# LED_driver_final.net
KiCad netlist of a schematic drawn in EAGLE
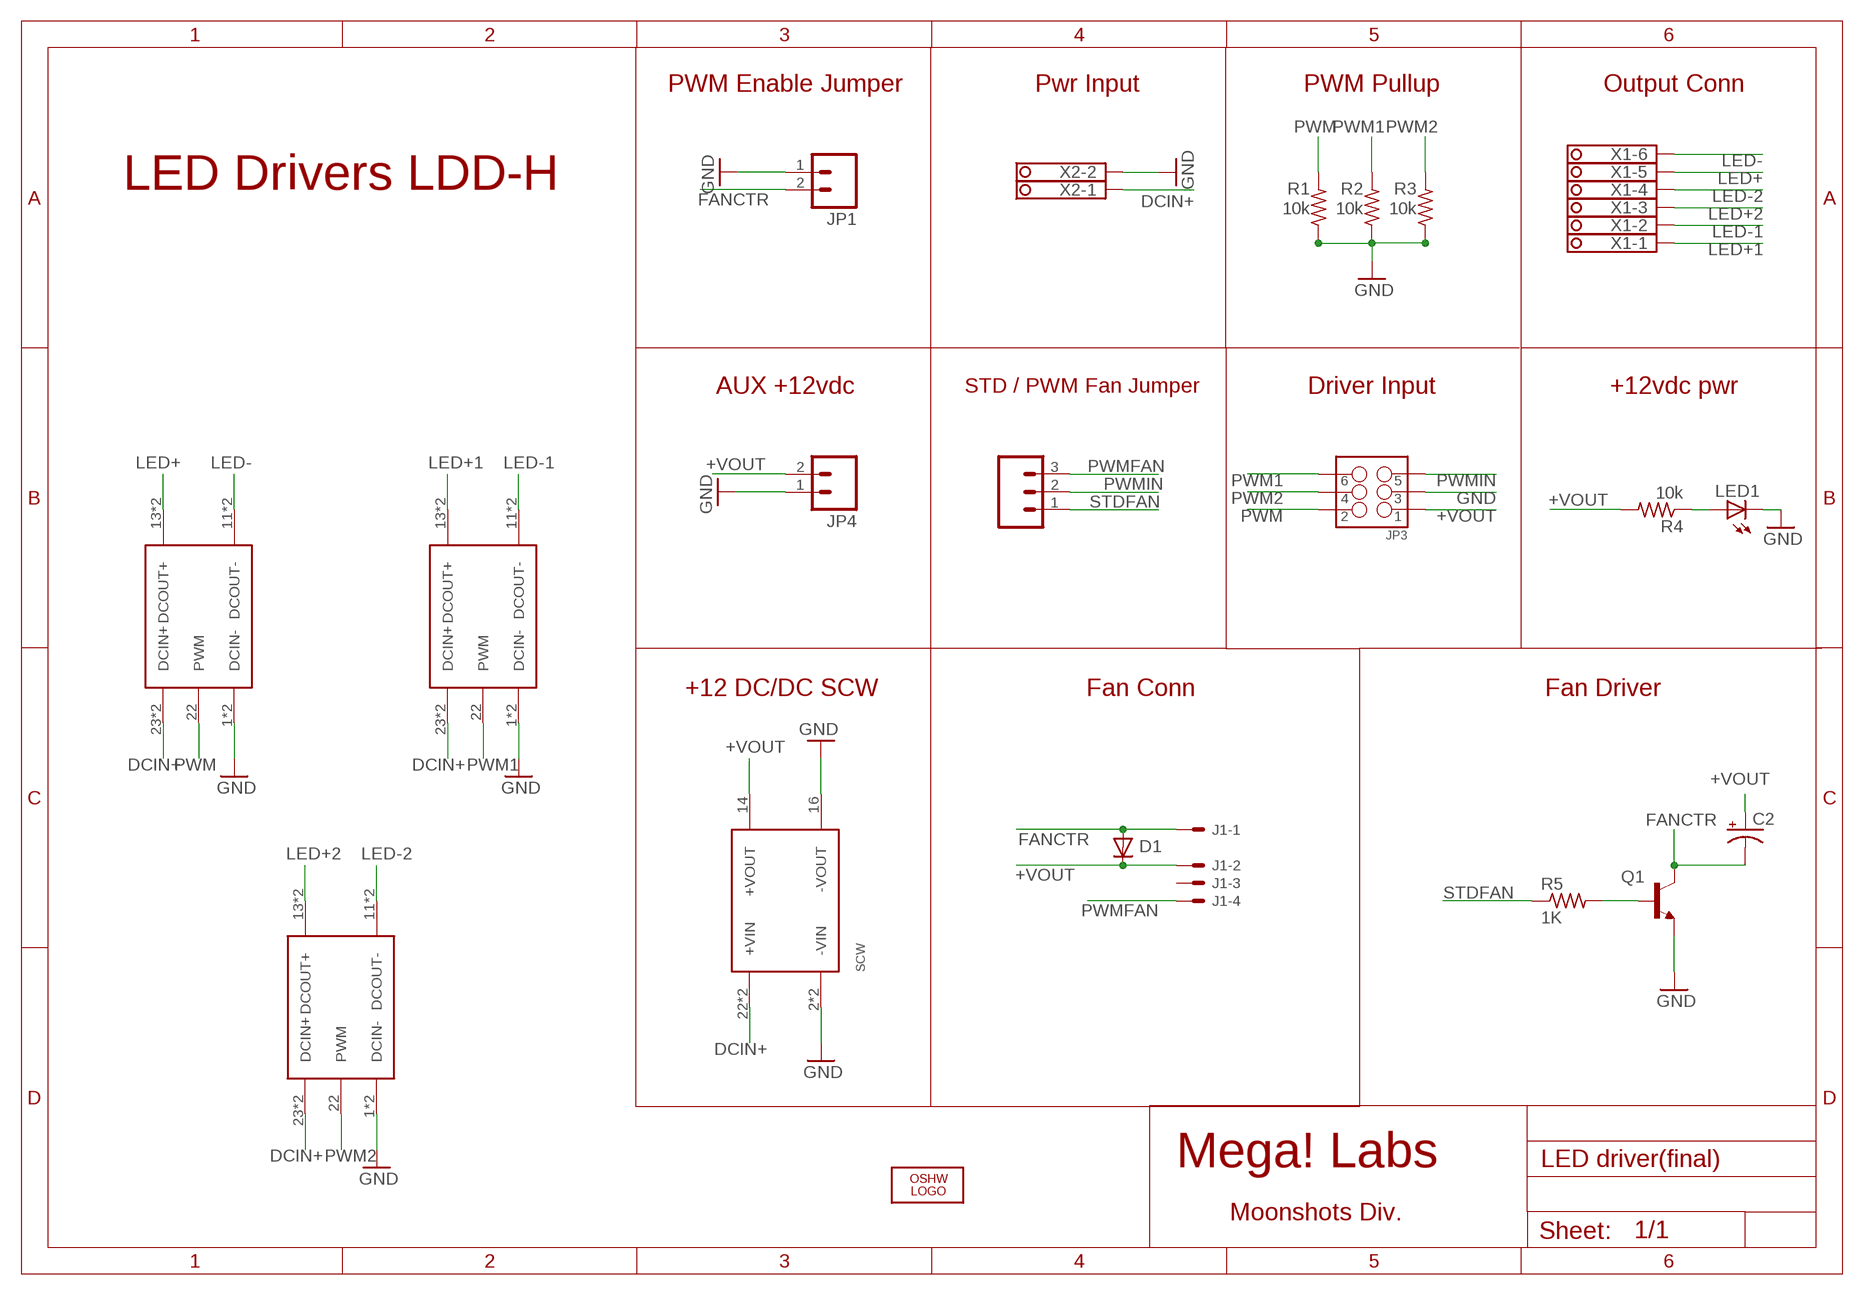
[diagram p0: schematic, sheet 1]

(export (version "E")
  (design (tool "Eeschema 10.0.6"))
  (components
    (comp (ref "C2")
      (value "CPOL-USE3.5-8")
      (footprint "eagle-import:E3,5-8")
      (libsource (lib "eagle-import") (part "CPOL-USE3.5-8"))
    )
    (comp (ref "D1")
      (value "CGRM4007-G")
      (footprint "eagle-import:SOD-123_MINI-SMA")
      (libsource (lib "eagle-import") (part "CGRM400-G7"))
    )
    (comp (ref "J1")
      (value "22-05-7048-04")
      (footprint "eagle-import:7395-04")
      (libsource (lib "eagle-import") (part "22-?-0405-7048"))
    )
    (comp (ref "JP1")
      (value "M02LOCK")
      (footprint "eagle-import:1X02_LOCK")
      (libsource (lib "eagle-import") (part "M02LOCK"))
    )
    (comp (ref "JP2")
      (value "M03LOCK")
      (footprint "eagle-import:1X03_LOCK")
      (libsource (lib "eagle-import") (part "M03LOCK"))
    )
    (comp (ref "JP3")
      (value "M03X2SHROUD")
      (footprint "eagle-import:2X3-SHROUDED")
      (libsource (lib "eagle-import") (part "M03X2SHROUD"))
    )
    (comp (ref "JP4")
      (value "M02-JST-2MM-SMT")
      (footprint "eagle-import:JST-2-SMD")
      (libsource (lib "eagle-import") (part "M02-JST-2MM-SMT"))
    )
    (comp (ref "LED1")
      (value "LEDCHIPLED_1206")
      (footprint "eagle-import:CHIPLED_1206")
      (libsource (lib "eagle-import") (part "LEDCHIPLED_1206"))
    )
    (comp (ref "LOGO2")
      (value "OSHW_LOGO_6MILX0150-NT")
      (footprint "eagle-import:OSHW_6X150_NOTEXT")
      (libsource (lib "eagle-import") (part "OSHW_LOGO_6MILX0150-NT"))
    )
    (comp (ref "Q1")
      (value "BC808-NPN-SOT23-BEC")
      (footprint "eagle-import:SOT23-BEC")
      (libsource (lib "eagle-import") (part "-NPN-SOT23-BECBC808"))
    )
    (comp (ref "R1")
      (value "10k")
      (footprint "eagle-import:M1206")
      (libsource (lib "eagle-import") (part "R-US_M1206"))
    )
    (comp (ref "R2")
      (value "10k")
      (footprint "eagle-import:M1206")
      (libsource (lib "eagle-import") (part "R-US_M1206"))
    )
    (comp (ref "R3")
      (value "10k")
      (footprint "eagle-import:M1206")
      (libsource (lib "eagle-import") (part "R-US_M1206"))
    )
    (comp (ref "R4")
      (value "10k")
      (footprint "eagle-import:M1206")
      (libsource (lib "eagle-import") (part "R-US_M1206"))
    )
    (comp (ref "R5")
      (value "1K")
      (footprint "eagle-import:M1206")
      (libsource (lib "eagle-import") (part "R-US_M1206"))
    )
    (comp (ref "U$1")
      (value "LDD_H")
      (footprint "eagle-import:LDD_H")
      (libsource (lib "eagle-import") (part "LDD_H"))
    )
    (comp (ref "U$2")
      (value "LDD_H")
      (footprint "eagle-import:LDD_H")
      (libsource (lib "eagle-import") (part "LDD_H"))
    )
    (comp (ref "U$3")
      (value "LDD_H")
      (footprint "eagle-import:LDD_H")
      (libsource (lib "eagle-import") (part "LDD_H"))
    )
    (comp (ref "U$5")
      (value "SCW")
      (footprint "eagle-import:SCW")
      (libsource (lib "eagle-import") (part "SCW"))
    )
    (comp (ref "X1")
      (value "1751280")
      (footprint "eagle-import:1751280")
      (libsource (lib "eagle-import") (part "1751280"))
    )
    (comp (ref "X2")
      (value "1751248")
      (footprint "eagle-import:1751248")
      (libsource (lib "eagle-import") (part "1751248"))
    )
  )
  (nets
    (net (code "1") (name "/+VOUT") (class "Default")
      (node (ref "C2") (pin "+") (pinfunction "+_+") (pintype "passive"))
      (node (ref "D1") (pin "C") (pinfunction "C_C") (pintype "passive"))
      (node (ref "J1") (pin "2") (pinfunction "S_2") (pintype "passive"))
      (node (ref "JP3") (pin "1") (pinfunction "1_1") (pintype "bidirectional"))
      (node (ref "JP4") (pin "2") (pinfunction "1_2") (pintype "passive"))
      (node (ref "R4") (pin "2") (pinfunction "2_2") (pintype "passive"))
      (node (ref "U$5") (pin "14") (pinfunction "+VOUT_14") (pintype "output"))
    )
    (net (code "2") (name "/DCIN+") (class "Default")
      (node (ref "U$1") (pin "23") (pinfunction "DCIN+_23") (pintype "input"))
      (node (ref "U$1") (pin "24") (pinfunction "DCIN+_24") (pintype "input"))
      (node (ref "U$2") (pin "23") (pinfunction "DCIN+_23") (pintype "input"))
      (node (ref "U$2") (pin "24") (pinfunction "DCIN+_24") (pintype "input"))
      (node (ref "U$3") (pin "23") (pinfunction "DCIN+_23") (pintype "input"))
      (node (ref "U$3") (pin "24") (pinfunction "DCIN+_24") (pintype "input"))
      (node (ref "U$5") (pin "22") (pinfunction "+VIN_22") (pintype "input"))
      (node (ref "U$5") (pin "23") (pinfunction "+VIN_23") (pintype "input"))
      (node (ref "X2") (pin "1") (pinfunction "K_1") (pintype "passive"))
    )
    (net (code "3") (name "/FANCTR") (class "Default")
      (node (ref "C2") (pin "-") (pinfunction "-_-") (pintype "passive"))
      (node (ref "D1") (pin "A") (pinfunction "A_A") (pintype "passive"))
      (node (ref "J1") (pin "1") (pinfunction "S_1") (pintype "passive"))
      (node (ref "JP1") (pin "2") (pinfunction "2_2") (pintype "passive"))
      (node (ref "Q1") (pin "C") (pinfunction "C_C") (pintype "passive"))
    )
    (net (code "4") (name "/LED+") (class "Default")
      (node (ref "U$1") (pin "13") (pinfunction "DCOUT+_13") (pintype "output"))
      (node (ref "U$1") (pin "14") (pinfunction "DCOUT+_14") (pintype "output"))
      (node (ref "X1") (pin "5") (pinfunction "K_5") (pintype "passive"))
    )
    (net (code "5") (name "/LED+1") (class "Default")
      (node (ref "U$2") (pin "13") (pinfunction "DCOUT+_13") (pintype "output"))
      (node (ref "U$2") (pin "14") (pinfunction "DCOUT+_14") (pintype "output"))
      (node (ref "X1") (pin "1") (pinfunction "K_1") (pintype "passive"))
    )
    (net (code "6") (name "/LED+2") (class "Default")
      (node (ref "U$3") (pin "13") (pinfunction "DCOUT+_13") (pintype "output"))
      (node (ref "U$3") (pin "14") (pinfunction "DCOUT+_14") (pintype "output"))
      (node (ref "X1") (pin "3") (pinfunction "K_3") (pintype "passive"))
    )
    (net (code "7") (name "/LED-") (class "Default")
      (node (ref "U$1") (pin "11") (pinfunction "DCOUT-_11") (pintype "output"))
      (node (ref "U$1") (pin "12") (pinfunction "DCOUT-_12") (pintype "output"))
      (node (ref "X1") (pin "6") (pinfunction "K_6") (pintype "passive"))
    )
    (net (code "8") (name "/LED-1") (class "Default")
      (node (ref "U$2") (pin "11") (pinfunction "DCOUT-_11") (pintype "output"))
      (node (ref "U$2") (pin "12") (pinfunction "DCOUT-_12") (pintype "output"))
      (node (ref "X1") (pin "2") (pinfunction "K_2") (pintype "passive"))
    )
    (net (code "9") (name "/LED-2") (class "Default")
      (node (ref "U$3") (pin "11") (pinfunction "DCOUT-_11") (pintype "output"))
      (node (ref "U$3") (pin "12") (pinfunction "DCOUT-_12") (pintype "output"))
      (node (ref "X1") (pin "4") (pinfunction "K_4") (pintype "passive"))
    )
    (net (code "10") (name "/PWM") (class "Default")
      (node (ref "JP3") (pin "2") (pinfunction "2_2") (pintype "bidirectional"))
      (node (ref "R1") (pin "2") (pinfunction "2_2") (pintype "passive"))
      (node (ref "U$1") (pin "22") (pinfunction "PWM_22") (pintype "bidirectional"))
    )
    (net (code "11") (name "/PWM1") (class "Default")
      (node (ref "JP3") (pin "6") (pinfunction "6_6") (pintype "bidirectional"))
      (node (ref "R2") (pin "2") (pinfunction "2_2") (pintype "passive"))
      (node (ref "U$2") (pin "22") (pinfunction "PWM_22") (pintype "bidirectional"))
    )
    (net (code "12") (name "/PWM2") (class "Default")
      (node (ref "JP3") (pin "4") (pinfunction "4_4") (pintype "bidirectional"))
      (node (ref "R3") (pin "2") (pinfunction "2_2") (pintype "passive"))
      (node (ref "U$3") (pin "22") (pinfunction "PWM_22") (pintype "bidirectional"))
    )
    (net (code "13") (name "/PWMFAN") (class "Default")
      (node (ref "J1") (pin "4") (pinfunction "S_4") (pintype "passive"))
      (node (ref "JP2") (pin "3") (pinfunction "3_3") (pintype "passive"))
    )
    (net (code "14") (name "/PWMIN") (class "Default")
      (node (ref "JP2") (pin "2") (pinfunction "2_2") (pintype "passive"))
      (node (ref "JP3") (pin "5") (pinfunction "5_5") (pintype "bidirectional"))
    )
    (net (code "15") (name "/STDFAN") (class "Default")
      (node (ref "JP2") (pin "1") (pinfunction "1_1") (pintype "passive"))
      (node (ref "R5") (pin "1") (pinfunction "1_1") (pintype "passive"))
    )
    (net (code "16") (name "GND") (class "Default")
      (node (ref "JP1") (pin "1") (pinfunction "1_1") (pintype "passive"))
      (node (ref "JP3") (pin "3") (pinfunction "3_3") (pintype "bidirectional"))
      (node (ref "JP4") (pin "1") (pinfunction "2_1") (pintype "passive"))
      (node (ref "LED1") (pin "C") (pinfunction "C_C") (pintype "passive"))
      (node (ref "Q1") (pin "E") (pinfunction "E_E") (pintype "passive"))
      (node (ref "R1") (pin "1") (pinfunction "1_1") (pintype "passive"))
      (node (ref "R2") (pin "1") (pinfunction "1_1") (pintype "passive"))
      (node (ref "R3") (pin "1") (pinfunction "1_1") (pintype "passive"))
      (node (ref "U$1") (pin "1") (pinfunction "DCIN-_1") (pintype "input"))
      (node (ref "U$1") (pin "2") (pinfunction "DCIN-_2") (pintype "input"))
      (node (ref "U$2") (pin "1") (pinfunction "DCIN-_1") (pintype "input"))
      (node (ref "U$2") (pin "2") (pinfunction "DCIN-_2") (pintype "input"))
      (node (ref "U$3") (pin "1") (pinfunction "DCIN-_1") (pintype "input"))
      (node (ref "U$3") (pin "2") (pinfunction "DCIN-_2") (pintype "input"))
      (node (ref "U$5") (pin "16") (pinfunction "-VOUT_16") (pintype "output"))
      (node (ref "U$5") (pin "2") (pinfunction "-VIN_2") (pintype "input"))
      (node (ref "U$5") (pin "3") (pinfunction "-VIN_3") (pintype "input"))
      (node (ref "X2") (pin "2") (pinfunction "K_2") (pintype "passive"))
    )
    (net (code "17") (name "Net-(LED1-PadA)") (class "Default")
      (node (ref "LED1") (pin "A") (pinfunction "A_A") (pintype "passive"))
      (node (ref "R4") (pin "1") (pinfunction "1_1") (pintype "passive"))
    )
    (net (code "18") (name "Net-(Q1-PadB)") (class "Default")
      (node (ref "Q1") (pin "B") (pinfunction "B_B") (pintype "passive"))
      (node (ref "R5") (pin "2") (pinfunction "2_2") (pintype "passive"))
    )
    (net (code "19") (name "unconnected-(J1C-S-Pad3)") (class "Default")
      (node (ref "J1") (pin "3") (pinfunction "S_3") (pintype "passive"))
    )
  )
)
